# MCU.net
KiCad netlist of a schematic drawn in Altium Designer
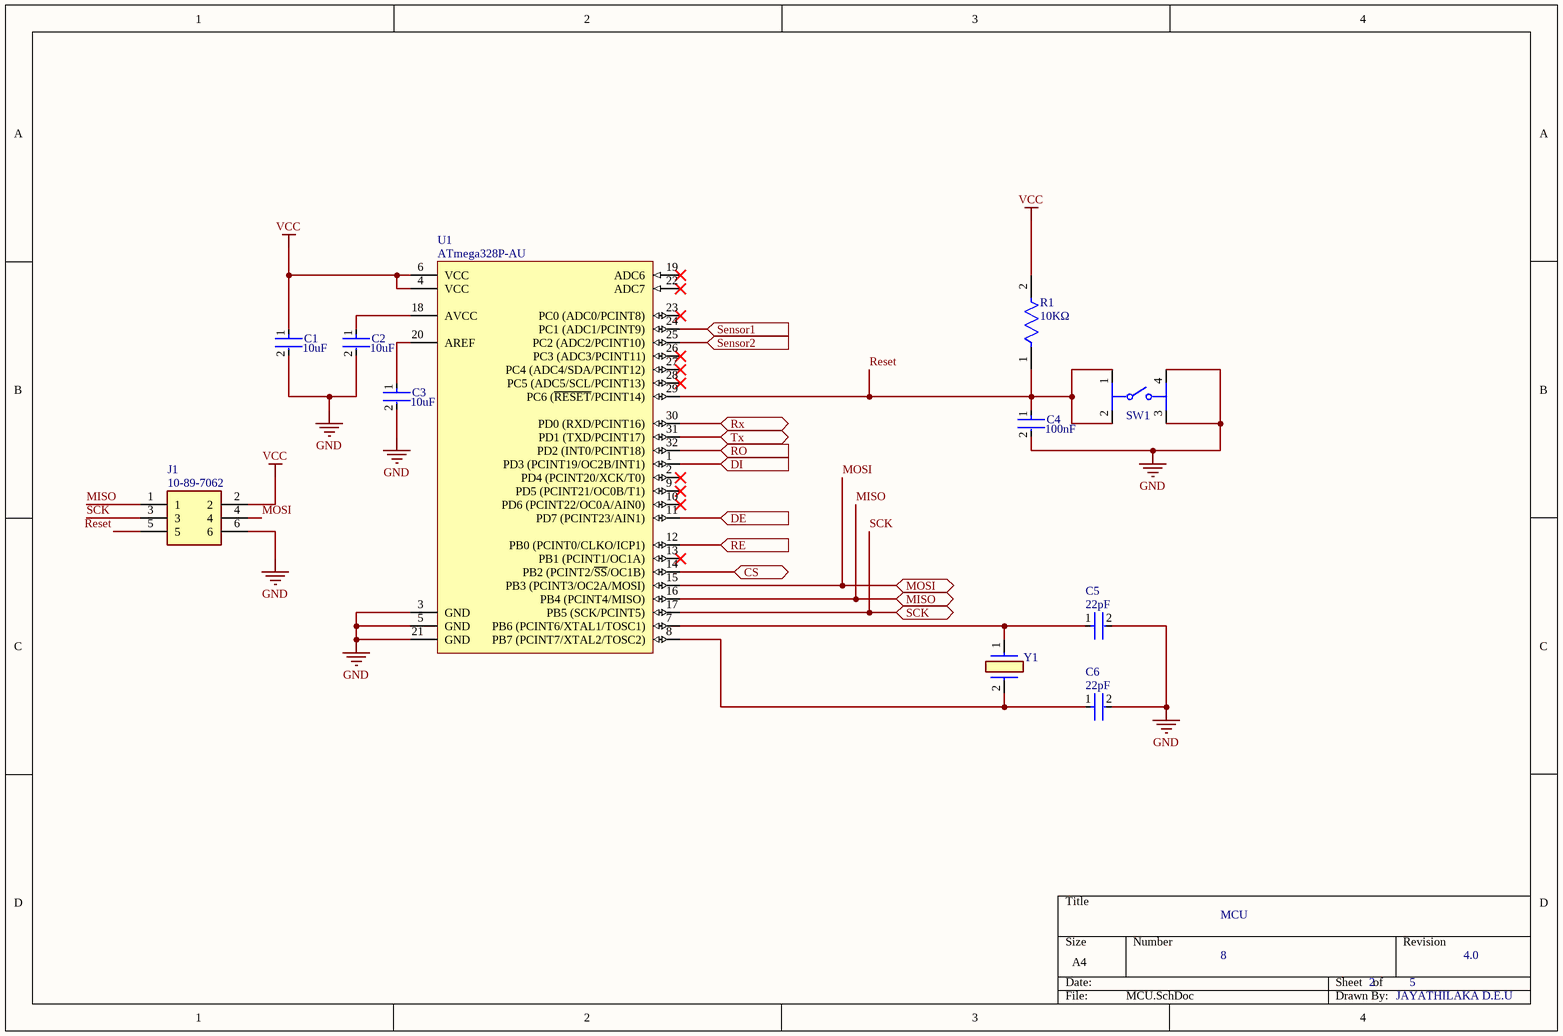
[diagram p0: MCU.SchDoc]

(export (version "E")
  (design (tool "Eeschema 10.0.6"))
  (components
    (comp (ref "C1")
      (value "10uF")
      (footprint "FP-CL31B106KBHNNNE-MFG")
      (description "CAP CER 10UF 50V X7R 1206")
      (fields (field (name "MANUFACTURER") "Samsung") (field (name "TOLERANCE") "10%"))
      (libsource (lib "Altium Content Vault") (part "b4654b650e69147ec39a6b967a45e02"))
    )
    (comp (ref "C2")
      (value "10uF")
      (footprint "FP-CL31B106KBHNNNE-MFG")
      (description "CAP CER 10UF 50V X7R 1206")
      (fields (field (name "MANUFACTURER") "Samsung") (field (name "TOLERANCE") "10%"))
      (libsource (lib "Altium Content Vault") (part "b4654b650e69147ec39a6b967a45e02"))
    )
    (comp (ref "C3")
      (value "10uF")
      (footprint "FP-CL31B106KBHNNNE-MFG")
      (description "CAP CER 10UF 50V X7R 1206")
      (fields (field (name "MANUFACTURER") "Samsung") (field (name "TOLERANCE") "10%"))
      (libsource (lib "Altium Content Vault") (part "b4654b650e69147ec39a6b967a45e02"))
    )
    (comp (ref "C4")
      (value "GRM31C5C1H104JA01L")
      (footprint "FP-GRM31C-0_2-e0_3_0_8-IPC_B")
      (description "Chip Multilayer Ceramic Capacitors for General Purpose, 1206, 0.10uF, C0G, 30ppm/°C, 5%, 50V")
      (fields
        (field (name "VOLTAGE") "50V")
        (field (name "CAPACITANCE") "100nF")
        (field (name "TOLERANCE") "5%")
      )
      (libsource (lib "Altium Content Vault") (part "02cd4be3c70576c341d710602a673aa"))
    )
    (comp (ref "C5")
      (value "GRM31A5C2J220JW01D")
      (footprint "FP-GRM31A-0_2-e0_3_0_95-IPC_C")
      (description "Chip Multilayer Ceramic Capacitors for General Purpose, 1206, 22pF, C0G, 30ppm/°C, 5%, 630V")
      (fields
        (field (name "TOLERANCE") "5%")
        (field (name "CAPACITANCE") "22pF")
        (field (name "VOLTAGE") "630V")
      )
      (libsource (lib "Altium Content Vault") (part "b4654b650e69147ec39a6b967a45e02"))
    )
    (comp (ref "C6")
      (value "GRM31A5C2J220JW01D")
      (footprint "FP-GRM31A-0_2-e0_3_0_95-IPC_C")
      (description "Chip Multilayer Ceramic Capacitors for General Purpose, 1206, 22pF, C0G, 30ppm/°C, 5%, 630V")
      (fields
        (field (name "TOLERANCE") "5%")
        (field (name "CAPACITANCE") "22pF")
        (field (name "VOLTAGE") "630V")
      )
      (libsource (lib "Altium Content Vault") (part "b4654b650e69147ec39a6b967a45e02"))
    )
    (comp (ref "J1")
      (value "10-89-7062")
      (footprint "SamacSys:HDRV6W87P254_2X3_775X508X864P")
      (description "Connector")
      (fields (field (name "MOUSER PART NUMBER") "538-10-89-7062"))
      (libsource (lib "*") (part "10-89-7062"))
    )
    (comp (ref "R1")
      (value "RT1206BRD0710KL")
      (footprint "FP-RT1206-MFG")
      (description "RES 10.0K OHM 1/4W .1% SMD 1206")
      (fields
        (field (name "OCTOPART") "https://octopart.com/rt1206brd0710kl-yageo-1397513")
        (field (name "RESISTANCE") "10KΩ")
        (field (name "MANUFACTURER") "Yageo")
      )
      (libsource (lib "Altium Content Vault") (part "1029c3af85768c4190bb7ad29bc67b5"))
    )
    (comp (ref "SW1")
      (value "1571634-2")
      (footprint "FP-1571634-2-MFG")
      (description "SWITCH TACTILE SPST-NO 0.05A 24V")
      (libsource (lib "Altium Content Vault") (part "512b1658425e80dc09bd29e095ee4d3"))
    )
    (comp (ref "U1")
      (value "ATmega328P-AU")
      (footprint "32A_M")
      (libsource (lib "Altium Content Vault") (part "MC-8B-ATM48-SQ32"))
    )
    (comp (ref "Y1")
      (value "ECS-160-20-3X-TR")
      (footprint "SamacSys:ECS160203XTR")
      (description "Crystal or Oscillator")
      (fields (field (name "MOUSER PART NUMBER") "520-160-20-3XT"))
      (libsource (lib "*") (part "ECS-160-20-3X-TR"))
    )
  )
  (nets
    (net (code "1") (name "/CS") (class "Default")
      (node (ref "U1") (pin "14") (pinfunction "PB2_(PCINT2/~{SS}/OC1B)_14") (pintype "bidirectional"))
    )
    (net (code "2") (name "/DE") (class "Default")
      (node (ref "U1") (pin "11") (pinfunction "PD7_(PCINT23/AIN1)_11") (pintype "bidirectional"))
    )
    (net (code "3") (name "/DI") (class "Default")
      (node (ref "U1") (pin "1") (pinfunction "PD3_(PCINT19/OC2B/INT1)_1") (pintype "bidirectional"))
    )
    (net (code "4") (name "/MISO") (class "Default")
      (node (ref "J1") (pin "1") (pinfunction "1_1") (pintype "passive"))
      (node (ref "U1") (pin "16") (pinfunction "PB4_(PCINT4/MISO)_16") (pintype "bidirectional"))
    )
    (net (code "5") (name "/MOSI") (class "Default")
      (node (ref "J1") (pin "4") (pinfunction "4_4") (pintype "passive"))
      (node (ref "U1") (pin "15") (pinfunction "PB3_(PCINT3/OC2A/MOSI)_15") (pintype "bidirectional"))
    )
    (net (code "6") (name "/RE") (class "Default")
      (node (ref "U1") (pin "12") (pinfunction "PB0_(PCINT0/CLKO/ICP1)_12") (pintype "bidirectional"))
    )
    (net (code "7") (name "/RO") (class "Default")
      (node (ref "U1") (pin "32") (pinfunction "PD2_(INT0/PCINT18)_32") (pintype "bidirectional"))
    )
    (net (code "8") (name "/Reset") (class "Default")
      (node (ref "C4") (pin "1") (pinfunction "1_1") (pintype "passive"))
      (node (ref "J1") (pin "5") (pinfunction "5_5") (pintype "passive"))
      (node (ref "R1") (pin "1") (pinfunction "1_1") (pintype "passive"))
      (node (ref "SW1") (pin "1") (pinfunction "1_1") (pintype "passive"))
      (node (ref "SW1") (pin "2") (pinfunction "2_2") (pintype "passive"))
      (node (ref "U1") (pin "29") (pinfunction "PC6_(~{RESET}/PCINT14)_29") (pintype "bidirectional"))
    )
    (net (code "9") (name "/Rx") (class "Default")
      (node (ref "U1") (pin "30") (pinfunction "PD0_(RXD/PCINT16)_30") (pintype "bidirectional"))
    )
    (net (code "10") (name "/SCK") (class "Default")
      (node (ref "J1") (pin "3") (pinfunction "3_3") (pintype "passive"))
      (node (ref "U1") (pin "17") (pinfunction "PB5_(SCK/PCINT5)_17") (pintype "bidirectional"))
    )
    (net (code "11") (name "/Sensor1") (class "Default")
      (node (ref "U1") (pin "24") (pinfunction "PC1_(ADC1/PCINT9)_24") (pintype "bidirectional"))
    )
    (net (code "12") (name "/Sensor2") (class "Default")
      (node (ref "U1") (pin "25") (pinfunction "PC2_(ADC2/PCINT10)_25") (pintype "bidirectional"))
    )
    (net (code "13") (name "/Tx") (class "Default")
      (node (ref "U1") (pin "31") (pinfunction "PD1_(TXD/PCINT17)_31") (pintype "bidirectional"))
    )
    (net (code "14") (name "GND") (class "Default")
      (node (ref "C1") (pin "2") (pinfunction "2_2") (pintype "passive"))
      (node (ref "C2") (pin "2") (pinfunction "2_2") (pintype "passive"))
      (node (ref "C3") (pin "2") (pinfunction "2_2") (pintype "passive"))
      (node (ref "C4") (pin "2") (pinfunction "2_2") (pintype "passive"))
      (node (ref "C5") (pin "2") (pinfunction "2_2") (pintype "passive"))
      (node (ref "C6") (pin "2") (pinfunction "2_2") (pintype "passive"))
      (node (ref "J1") (pin "6") (pinfunction "6_6") (pintype "passive"))
      (node (ref "SW1") (pin "3") (pinfunction "3_3") (pintype "passive"))
      (node (ref "SW1") (pin "4") (pinfunction "4_4") (pintype "passive"))
      (node (ref "U1") (pin "21") (pinfunction "GND_21") (pintype "power_in"))
      (node (ref "U1") (pin "3") (pinfunction "GND_3") (pintype "power_in"))
      (node (ref "U1") (pin "5") (pinfunction "GND_5") (pintype "power_in"))
    )
    (net (code "15") (name "Net-(U1-AREF)") (class "Default")
      (node (ref "C3") (pin "1") (pinfunction "1_1") (pintype "passive"))
      (node (ref "U1") (pin "20") (pinfunction "AREF_20") (pintype "passive"))
    )
    (net (code "16") (name "Net-(U1-AVCC)") (class "Default")
      (node (ref "C2") (pin "1") (pinfunction "1_1") (pintype "passive"))
      (node (ref "U1") (pin "18") (pinfunction "AVCC_18") (pintype "power_in"))
    )
    (net (code "17") (name "Net-(U1-PB6_(PCINT6{slash}XTAL1{slash}TOSC1))") (class "Default")
      (node (ref "C5") (pin "1") (pinfunction "1_1") (pintype "passive"))
      (node (ref "U1") (pin "7") (pinfunction "PB6_(PCINT6/XTAL1/TOSC1)_7") (pintype "bidirectional"))
      (node (ref "Y1") (pin "1") (pinfunction "X1_1") (pintype "passive"))
    )
    (net (code "18") (name "Net-(U1-PB7_(PCINT7{slash}XTAL2{slash}TOSC2))") (class "Default")
      (node (ref "C6") (pin "1") (pinfunction "1_1") (pintype "passive"))
      (node (ref "U1") (pin "8") (pinfunction "PB7_(PCINT7/XTAL2/TOSC2)_8") (pintype "bidirectional"))
      (node (ref "Y1") (pin "2") (pinfunction "X2_2") (pintype "passive"))
    )
    (net (code "19") (name "VCC") (class "Default")
      (node (ref "C1") (pin "1") (pinfunction "1_1") (pintype "passive"))
      (node (ref "J1") (pin "2") (pinfunction "2_2") (pintype "passive"))
      (node (ref "R1") (pin "2") (pinfunction "2_2") (pintype "passive"))
      (node (ref "U1") (pin "4") (pinfunction "VCC_4") (pintype "power_in"))
      (node (ref "U1") (pin "6") (pinfunction "VCC_6") (pintype "power_in"))
    )
    (net (code "20") (name "unconnected-(U1-ADC6-Pad19)") (class "Default")
      (node (ref "U1") (pin "19") (pinfunction "ADC6_19") (pintype "input+no_connect"))
    )
    (net (code "21") (name "unconnected-(U1-ADC7-Pad22)") (class "Default")
      (node (ref "U1") (pin "22") (pinfunction "ADC7_22") (pintype "input+no_connect"))
    )
    (net (code "22") (name "unconnected-(U1-PB1_(PCINT1{slash}OC1A)-Pad13)") (class "Default")
      (node (ref "U1") (pin "13") (pinfunction "PB1_(PCINT1/OC1A)_13") (pintype "bidirectional+no_connect"))
    )
    (net (code "23") (name "unconnected-(U1-PC0_(ADC0{slash}PCINT8)-Pad23)") (class "Default")
      (node (ref "U1") (pin "23") (pinfunction "PC0_(ADC0/PCINT8)_23") (pintype "bidirectional+no_connect"))
    )
    (net (code "24") (name "unconnected-(U1-PC3_(ADC3{slash}PCINT11)-Pad26)") (class "Default")
      (node (ref "U1") (pin "26") (pinfunction "PC3_(ADC3/PCINT11)_26") (pintype "bidirectional+no_connect"))
    )
    (net (code "25") (name "unconnected-(U1-PC4_(ADC4{slash}SDA{slash}PCINT12)-Pad27)") (class "Default")
      (node (ref "U1") (pin "27") (pinfunction "PC4_(ADC4/SDA/PCINT12)_27") (pintype "bidirectional+no_connect"))
    )
    (net (code "26") (name "unconnected-(U1-PC5_(ADC5{slash}SCL{slash}PCINT13)-Pad28)") (class "Default")
      (node (ref "U1") (pin "28") (pinfunction "PC5_(ADC5/SCL/PCINT13)_28") (pintype "bidirectional+no_connect"))
    )
    (net (code "27") (name "unconnected-(U1-PD4_(PCINT20{slash}XCK{slash}T0)-Pad2)") (class "Default")
      (node (ref "U1") (pin "2") (pinfunction "PD4_(PCINT20/XCK/T0)_2") (pintype "bidirectional+no_connect"))
    )
    (net (code "28") (name "unconnected-(U1-PD5_(PCINT21{slash}OC0B{slash}T1)-Pad9)") (class "Default")
      (node (ref "U1") (pin "9") (pinfunction "PD5_(PCINT21/OC0B/T1)_9") (pintype "bidirectional+no_connect"))
    )
    (net (code "29") (name "unconnected-(U1-PD6_(PCINT22{slash}OC0A{slash}AIN0)-Pad10)") (class "Default")
      (node (ref "U1") (pin "10") (pinfunction "PD6_(PCINT22/OC0A/AIN0)_10") (pintype "bidirectional+no_connect"))
    )
  )
)
